# TMC7300.net
KiCad netlist of a schematic drawn in Altium Designer
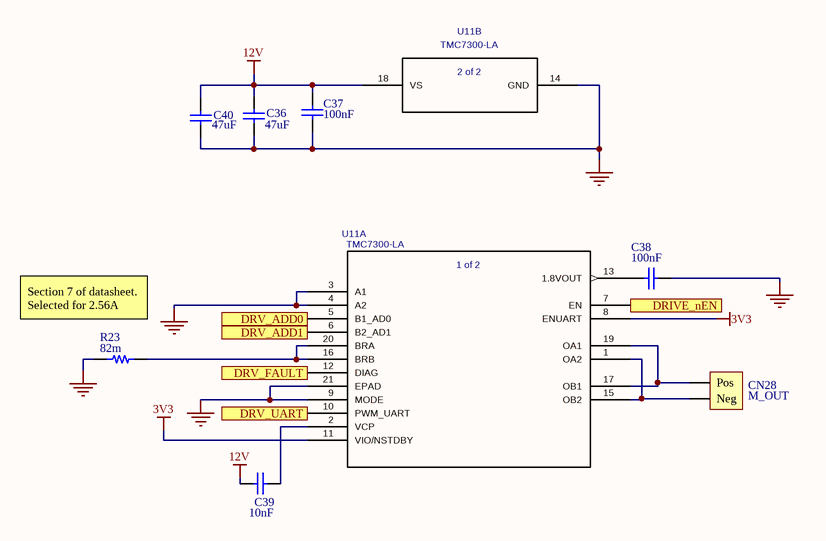
[diagram p0: TMC7300.SchDoc]

(export (version "E")
  (design (tool "Eeschema 10.0.6"))
  (components
    (comp (ref "C36")
      (value "47uF")
      (footprint "1206")
      (fields (field (name "Comment") "Cap") (field (name "PUBLISHER") "Altium Limited"))
      (libsource (lib "Parts") (part "Cap"))
    )
    (comp (ref "C37")
      (value "100nF")
      (footprint "0402")
      (fields (field (name "PUBLISHER") "Altium Limited"))
      (libsource (lib "Parts") (part "Cap"))
    )
    (comp (ref "C38")
      (value "100nF")
      (footprint "0402")
      (fields (field (name "Comment") "Cap") (field (name "PUBLISHER") "Altium Limited"))
      (libsource (lib "Parts") (part "Cap"))
    )
    (comp (ref "C39")
      (value "10nF")
      (footprint "0402")
      (fields (field (name "Comment") "Cap") (field (name "PUBLISHER") "Altium Limited"))
      (libsource (lib "Parts") (part "Cap"))
    )
    (comp (ref "C40")
      (value "47uF")
      (footprint "1206")
      (fields (field (name "Comment") "Cap") (field (name "PUBLISHER") "Altium Limited"))
      (libsource (lib "Parts") (part "Cap"))
    )
    (comp (ref "CN28")
      (value "M_OUT")
      (footprint "Power_Leads")
      (libsource (lib "Parts") (part "JST_Leads_In"))
    )
    (comp (ref "R23")
      (value "82m")
      (footprint "2010_SMD_Resistor")
      (libsource (lib "Parts") (part "Resistor"))
    )
    (comp (ref "U11")
      (value "TMC7300-LA")
      (footprint "QFN20_3X3")
      (fields (field (name "COPYRIGHT") "Copyright (C) 2018 Accelerated Designs. All rights reserved"))
      (libsource (lib "Parts") (part "TMC7300-LA"))
    )
  )
  (nets
    (net (code "1") (name "/DRIVE_nEN") (class "Default")
      (node (ref "U11") (pin "7") (pinfunction "EN_7") (pintype "passive"))
    )
    (net (code "2") (name "/DRV_ADD0") (class "Default")
      (node (ref "U11") (pin "5") (pinfunction "B1_AD0_5") (pintype "passive"))
    )
    (net (code "3") (name "/DRV_ADD1") (class "Default")
      (node (ref "U11") (pin "6") (pinfunction "B2_AD1_6") (pintype "passive"))
    )
    (net (code "4") (name "/DRV_FAULT") (class "Default")
      (node (ref "U11") (pin "12") (pinfunction "DIAG_12") (pintype "passive"))
    )
    (net (code "5") (name "/DRV_UART") (class "Default")
      (node (ref "U11") (pin "10") (pinfunction "PWM_UART_10") (pintype "passive"))
    )
    (net (code "6") (name "3V3") (class "Default")
      (node (ref "U11") (pin "11") (pinfunction "VIO/NSTDBY_11") (pintype "passive"))
      (node (ref "U11") (pin "8") (pinfunction "ENUART_8") (pintype "passive"))
    )
    (net (code "7") (name "12V") (class "Default")
      (node (ref "C36") (pin "2") (pinfunction "2_2") (pintype "passive"))
      (node (ref "C37") (pin "2") (pinfunction "2_2") (pintype "passive"))
      (node (ref "C39") (pin "1") (pinfunction "1_1") (pintype "passive"))
      (node (ref "C40") (pin "2") (pinfunction "2_2") (pintype "passive"))
      (node (ref "U11") (pin "18") (pinfunction "VS_18") (pintype "power_in"))
    )
    (net (code "8") (name "GND") (class "Default")
      (node (ref "C36") (pin "1") (pinfunction "1_1") (pintype "passive"))
      (node (ref "C37") (pin "1") (pinfunction "1_1") (pintype "passive"))
      (node (ref "C38") (pin "2") (pinfunction "2_2") (pintype "passive"))
      (node (ref "C40") (pin "1") (pinfunction "1_1") (pintype "passive"))
      (node (ref "R23") (pin "1") (pinfunction "1_1") (pintype "passive"))
      (node (ref "U11") (pin "14") (pinfunction "GND_14") (pintype "power_in"))
      (node (ref "U11") (pin "21") (pinfunction "EPAD_21") (pintype "passive"))
      (node (ref "U11") (pin "3") (pinfunction "A1_3") (pintype "passive"))
      (node (ref "U11") (pin "4") (pinfunction "A2_4") (pintype "passive"))
      (node (ref "U11") (pin "9") (pinfunction "MODE_9") (pintype "passive"))
    )
    (net (code "9") (name "Net-(CN28-Neg)") (class "Default")
      (node (ref "CN28") (pin "K") (pinfunction "Neg_K") (pintype "passive"))
      (node (ref "U11") (pin "1") (pinfunction "OA2_1") (pintype "passive"))
      (node (ref "U11") (pin "15") (pinfunction "OB2_15") (pintype "passive"))
    )
    (net (code "10") (name "Net-(CN28-Pos)") (class "Default")
      (node (ref "CN28") (pin "A") (pinfunction "Pos_A") (pintype "passive"))
      (node (ref "U11") (pin "17") (pinfunction "OB1_17") (pintype "passive"))
      (node (ref "U11") (pin "19") (pinfunction "OA1_19") (pintype "passive"))
    )
    (net (code "11") (name "Net-(U11A-1.8VOUT)") (class "Default")
      (node (ref "C38") (pin "1") (pinfunction "1_1") (pintype "passive"))
      (node (ref "U11") (pin "13") (pinfunction "1.8VOUT_13") (pintype "output"))
    )
    (net (code "12") (name "Net-(U11A-BRA)") (class "Default")
      (node (ref "R23") (pin "2") (pinfunction "2_2") (pintype "passive"))
      (node (ref "U11") (pin "16") (pinfunction "BRB_16") (pintype "passive"))
      (node (ref "U11") (pin "20") (pinfunction "BRA_20") (pintype "passive"))
    )
    (net (code "13") (name "Net-(U11A-VCP)") (class "Default")
      (node (ref "C39") (pin "2") (pinfunction "2_2") (pintype "passive"))
      (node (ref "U11") (pin "2") (pinfunction "VCP_2") (pintype "passive"))
    )
  )
)
